# child3.net
KiCad netlist of a schematic drawn in Altium Designer
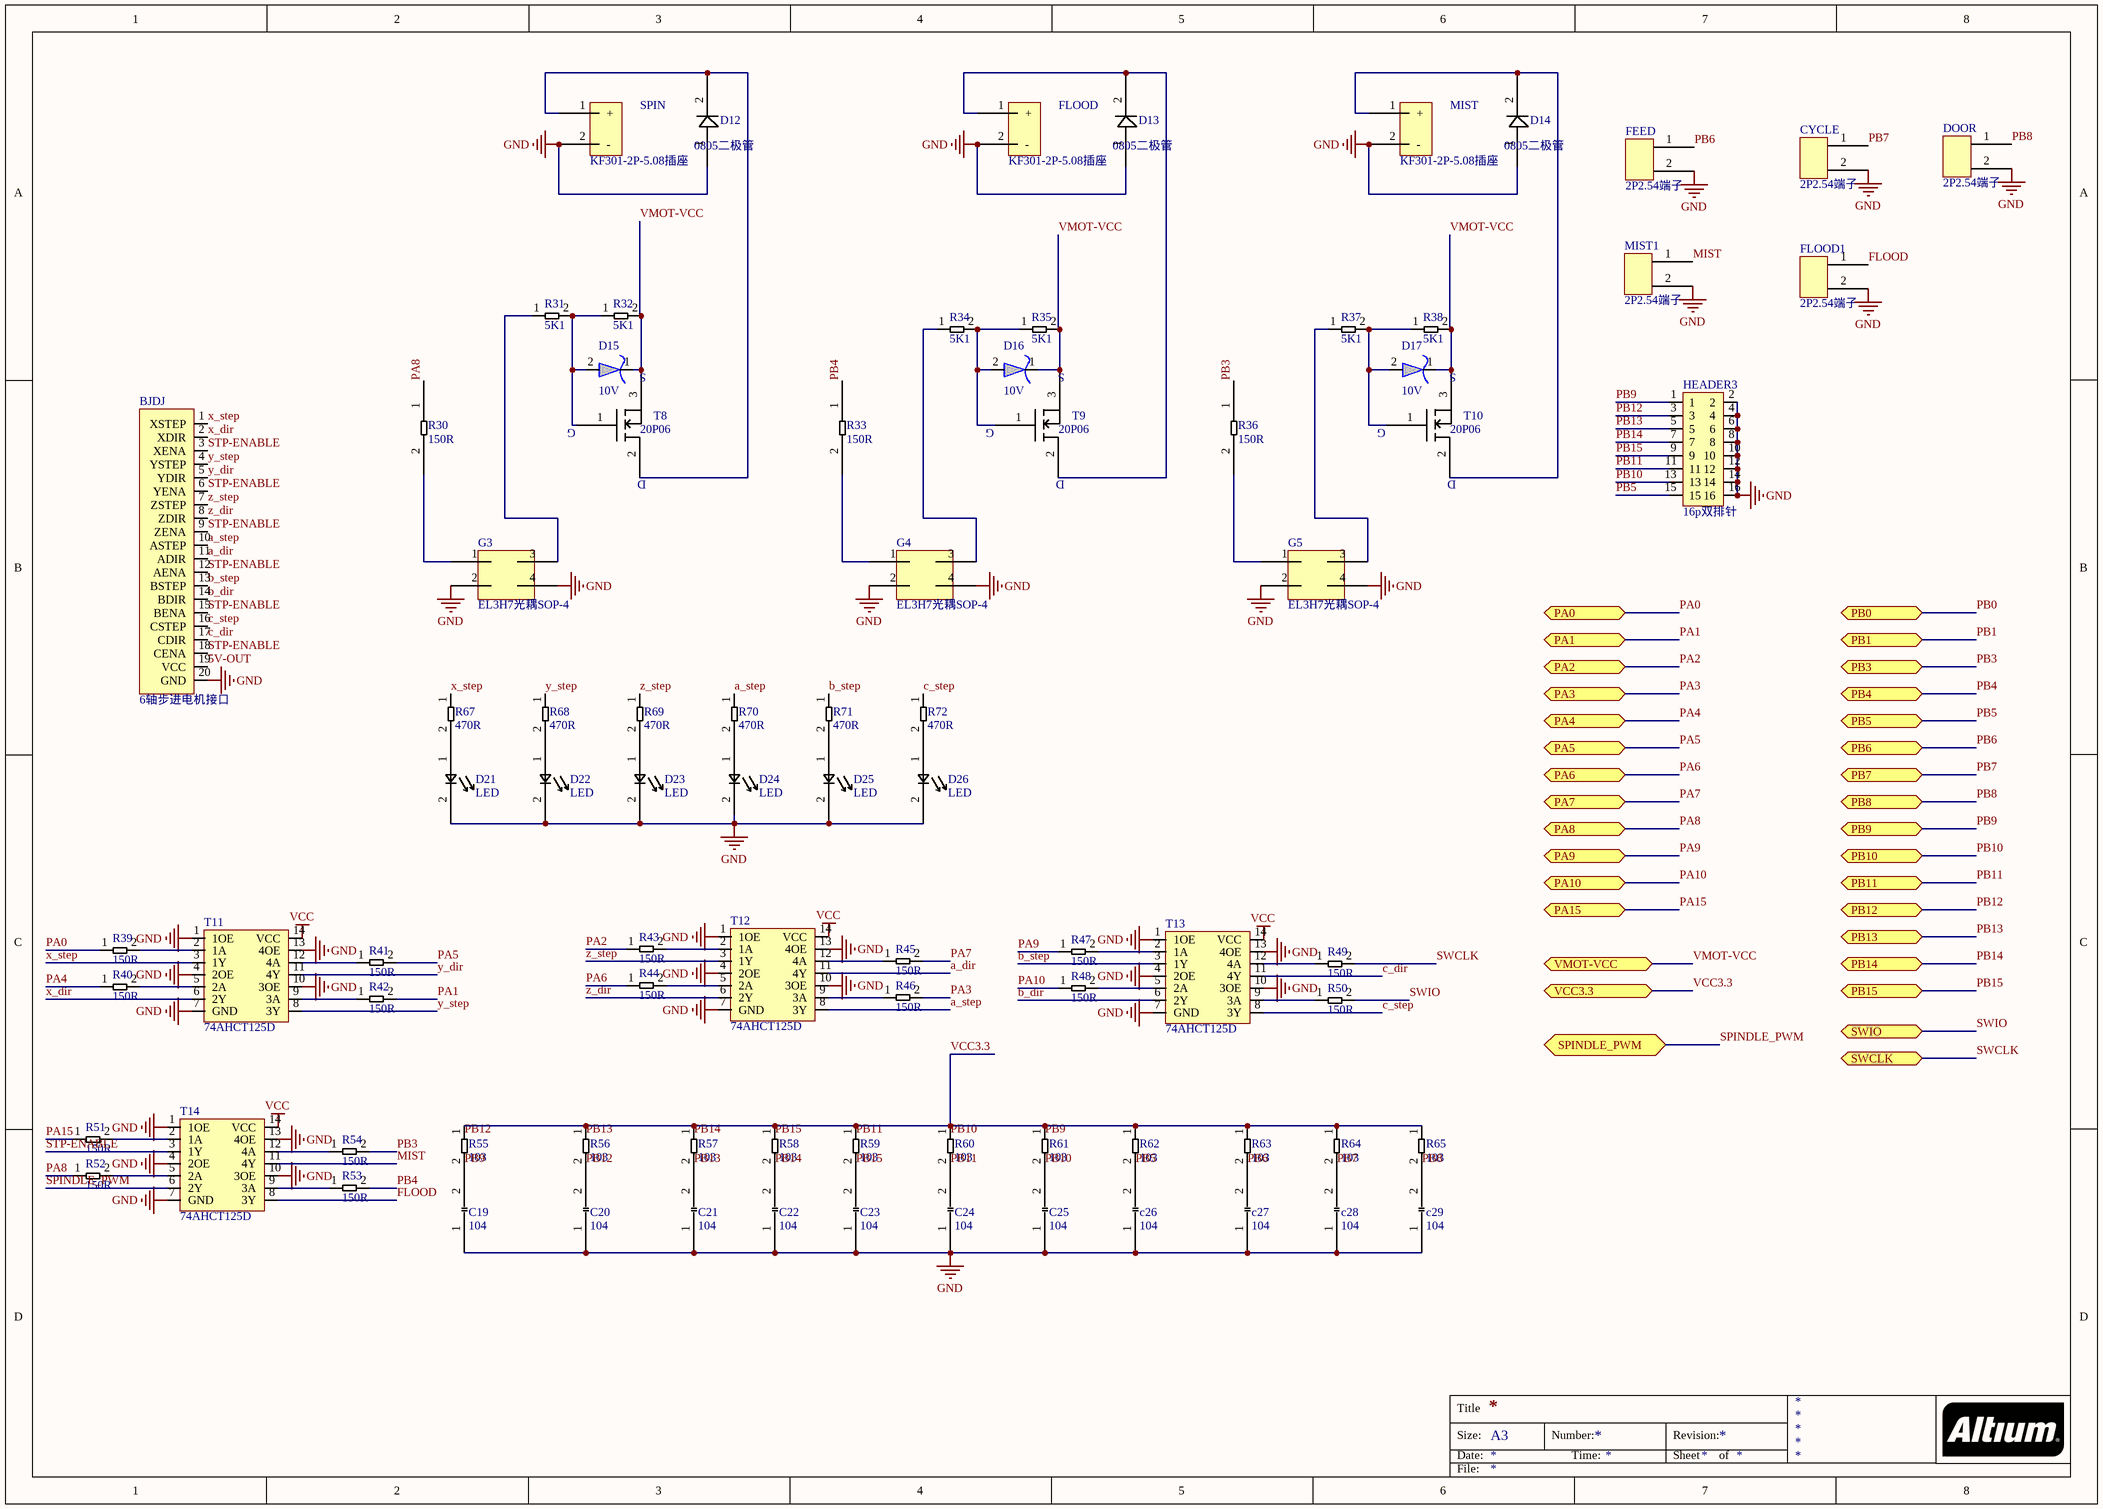
[diagram p0: child3.SchDoc]

(export (version "E")
  (design (tool "Eeschema 10.0.6"))
  (components
    (comp (ref "BJDJ") (value "6轴步进电机接口") (footprint "KF301-20P") (libsource (lib "51单片机") (part "6轴步进电机接口")))
    (comp (ref "C19") (value "104") (footprint "0805电容") (libsource (lib "51单片机") (part "0805贴片电容")))
    (comp (ref "C20") (value "104") (footprint "0805电容") (libsource (lib "51单片机") (part "0805贴片电容")))
    (comp (ref "C21") (value "104") (footprint "0805电容") (libsource (lib "51单片机") (part "0805贴片电容")))
    (comp (ref "C22") (value "104") (footprint "0805电容") (libsource (lib "51单片机") (part "0805贴片电容")))
    (comp (ref "C23") (value "104") (footprint "0805电容") (libsource (lib "51单片机") (part "0805贴片电容")))
    (comp (ref "C24") (value "104") (footprint "0805电容") (libsource (lib "51单片机") (part "0805贴片电容")))
    (comp (ref "C25") (value "104") (footprint "0805电容") (libsource (lib "51单片机") (part "0805贴片电容")))
    (comp (ref "c26") (value "104") (footprint "0805电容") (libsource (lib "51单片机") (part "0805贴片电容")))
    (comp (ref "c27") (value "104") (footprint "0805电容") (libsource (lib "51单片机") (part "0805贴片电容")))
    (comp (ref "c28") (value "104") (footprint "0805电容") (libsource (lib "51单片机") (part "0805贴片电容")))
    (comp (ref "c29") (value "104") (footprint "0805电容") (libsource (lib "51单片机") (part "0805贴片电容")))
    (comp (ref "CYCLE") (value "2P2.54端子") (footprint "2p2.54端子") (libsource (lib "51单片机") (part "2P2.54端子")))
    (comp (ref "D12") (value "0805二极管") (footprint "0805-二极管") (libsource (lib "51单片机") (part "0805二极管")))
    (comp (ref "D13") (value "0805二极管") (footprint "0805-二极管") (libsource (lib "51单片机") (part "0805二极管")))
    (comp (ref "D14") (value "0805二极管") (footprint "0805-二极管") (libsource (lib "51单片机") (part "0805二极管")))
    (comp (ref "D15") (value "10V") (footprint "1/2w贴片稳压二极管") (libsource (lib "51单片机") (part "贴片稳压二极管")))
    (comp (ref "D16") (value "10V") (footprint "1/2w贴片稳压二极管") (libsource (lib "51单片机") (part "贴片稳压二极管")))
    (comp (ref "D17") (value "10V") (footprint "1/2w贴片稳压二极管") (libsource (lib "51单片机") (part "贴片稳压二极管")))
    (comp (ref "D21") (value "LED") (footprint "0805二极管") (libsource (lib "51单片机") (part "0805贴片发光二极管")))
    (comp (ref "D22") (value "LED") (footprint "0805二极管") (libsource (lib "51单片机") (part "0805贴片发光二极管")))
    (comp (ref "D23") (value "LED") (footprint "0805二极管") (libsource (lib "51单片机") (part "0805贴片发光二极管")))
    (comp (ref "D24") (value "LED") (footprint "0805二极管") (libsource (lib "51单片机") (part "0805贴片发光二极管")))
    (comp (ref "D25") (value "LED") (footprint "0805二极管") (libsource (lib "51单片机") (part "0805贴片发光二极管")))
    (comp (ref "D26") (value "LED") (footprint "0805二极管") (libsource (lib "51单片机") (part "0805贴片发光二极管")))
    (comp (ref "DOOR") (value "2P2.54端子") (footprint "2p2.54端子") (libsource (lib "51单片机") (part "2P2.54端子")))
    (comp (ref "FEED") (value "2P2.54端子") (footprint "2p2.54端子") (libsource (lib "51单片机") (part "2P2.54端子")))
    (comp (ref "FLOOD")
      (value "KF301-2P-5.08插座")
      (footprint "KF301-2P-5.08插座")
      (libsource (lib "51单片机") (part "KF301-2P-5.08插座"))
    )
    (comp (ref "FLOOD1")
      (value "2P2.54端子")
      (footprint "2p2.54端子")
      (libsource (lib "51单片机") (part "2P2.54端子"))
    )
    (comp (ref "G3")
      (value "EL3H7光耦SOP-4")
      (footprint "EL3H7SOP-4")
      (libsource (lib "51单片机") (part "EL3H7光耦SOP-4"))
    )
    (comp (ref "G4")
      (value "EL3H7光耦SOP-4")
      (footprint "EL3H7SOP-4")
      (libsource (lib "51单片机") (part "EL3H7光耦SOP-4"))
    )
    (comp (ref "G5")
      (value "EL3H7光耦SOP-4")
      (footprint "EL3H7SOP-4")
      (libsource (lib "51单片机") (part "EL3H7光耦SOP-4"))
    )
    (comp (ref "HEADER3") (value "16p双排针") (footprint "16p双排针") (libsource (lib "51单片机") (part "16p双排针")))
    (comp (ref "MIST")
      (value "KF301-2P-5.08插座")
      (footprint "KF301-2P-5.08插座")
      (libsource (lib "51单片机") (part "KF301-2P-5.08插座"))
    )
    (comp (ref "MIST1") (value "2P2.54端子") (footprint "2p2.54端子") (libsource (lib "51单片机") (part "2P2.54端子")))
    (comp (ref "R30") (value "150R") (footprint "0805电阻") (libsource (lib "") (part "0805贴片电阻_1")))
    (comp (ref "R31") (value "5K1") (footprint "0805电阻") (libsource (lib "51单片机") (part "0805贴片电阻")))
    (comp (ref "R32") (value "5K1") (footprint "0805电阻") (libsource (lib "51单片机") (part "0805贴片电阻")))
    (comp (ref "R33") (value "150R") (footprint "0805电阻") (libsource (lib "") (part "0805贴片电阻_1")))
    (comp (ref "R34") (value "5K1") (footprint "0805电阻") (libsource (lib "51单片机") (part "0805贴片电阻")))
    (comp (ref "R35") (value "5K1") (footprint "0805电阻") (libsource (lib "51单片机") (part "0805贴片电阻")))
    (comp (ref "R36") (value "150R") (footprint "0805电阻") (libsource (lib "") (part "0805贴片电阻_1")))
    (comp (ref "R37") (value "5K1") (footprint "0805电阻") (libsource (lib "51单片机") (part "0805贴片电阻")))
    (comp (ref "R38") (value "5K1") (footprint "0805电阻") (libsource (lib "51单片机") (part "0805贴片电阻")))
    (comp (ref "R39") (value "150R") (footprint "0805电阻") (libsource (lib "51单片机") (part "0805贴片电阻")))
    (comp (ref "R40") (value "150R") (footprint "0805电阻") (libsource (lib "51单片机") (part "0805贴片电阻")))
    (comp (ref "R41") (value "150R") (footprint "0805电阻") (libsource (lib "51单片机") (part "0805贴片电阻")))
    (comp (ref "R42") (value "150R") (footprint "0805电阻") (libsource (lib "51单片机") (part "0805贴片电阻")))
    (comp (ref "R43") (value "150R") (footprint "0805电阻") (libsource (lib "51单片机") (part "0805贴片电阻")))
    (comp (ref "R44") (value "150R") (footprint "0805电阻") (libsource (lib "51单片机") (part "0805贴片电阻")))
    (comp (ref "R45") (value "150R") (footprint "0805电阻") (libsource (lib "51单片机") (part "0805贴片电阻")))
    (comp (ref "R46") (value "150R") (footprint "0805电阻") (libsource (lib "51单片机") (part "0805贴片电阻")))
    (comp (ref "R47") (value "150R") (footprint "0805电阻") (libsource (lib "51单片机") (part "0805贴片电阻")))
    (comp (ref "R48") (value "150R") (footprint "0805电阻") (libsource (lib "51单片机") (part "0805贴片电阻")))
    (comp (ref "R49") (value "150R") (footprint "0805电阻") (libsource (lib "51单片机") (part "0805贴片电阻")))
    (comp (ref "R50") (value "150R") (footprint "0805电阻") (libsource (lib "51单片机") (part "0805贴片电阻")))
    (comp (ref "R51") (value "150R") (footprint "0805电阻") (libsource (lib "51单片机") (part "0805贴片电阻")))
    (comp (ref "R52") (value "150R") (footprint "0805电阻") (libsource (lib "51单片机") (part "0805贴片电阻")))
    (comp (ref "R53") (value "150R") (footprint "0805电阻") (libsource (lib "51单片机") (part "0805贴片电阻")))
    (comp (ref "R54") (value "150R") (footprint "0805电阻") (libsource (lib "51单片机") (part "0805贴片电阻")))
    (comp (ref "R55") (value "103") (footprint "0805电阻") (libsource (lib "51单片机") (part "0805贴片电阻")))
    (comp (ref "R56") (value "103") (footprint "0805电阻") (libsource (lib "51单片机") (part "0805贴片电阻")))
    (comp (ref "R57") (value "103") (footprint "0805电阻") (libsource (lib "51单片机") (part "0805贴片电阻")))
    (comp (ref "R58") (value "103") (footprint "0805电阻") (libsource (lib "51单片机") (part "0805贴片电阻")))
    (comp (ref "R59") (value "103") (footprint "0805电阻") (libsource (lib "51单片机") (part "0805贴片电阻")))
    (comp (ref "R60") (value "103") (footprint "0805电阻") (libsource (lib "51单片机") (part "0805贴片电阻")))
    (comp (ref "R61") (value "103") (footprint "0805电阻") (libsource (lib "51单片机") (part "0805贴片电阻")))
    (comp (ref "R62") (value "103") (footprint "0805电阻") (libsource (lib "51单片机") (part "0805贴片电阻")))
    (comp (ref "R63") (value "103") (footprint "0805电阻") (libsource (lib "51单片机") (part "0805贴片电阻")))
    (comp (ref "R64") (value "103") (footprint "0805电阻") (libsource (lib "51单片机") (part "0805贴片电阻")))
    (comp (ref "R65") (value "103") (footprint "0805电阻") (libsource (lib "51单片机") (part "0805贴片电阻")))
    (comp (ref "R67") (value "470R") (footprint "0805电阻") (libsource (lib "51单片机") (part "0805贴片电阻")))
    (comp (ref "R68") (value "470R") (footprint "0805电阻") (libsource (lib "51单片机") (part "0805贴片电阻")))
    (comp (ref "R69") (value "470R") (footprint "0805电阻") (libsource (lib "51单片机") (part "0805贴片电阻")))
    (comp (ref "R70") (value "470R") (footprint "0805电阻") (libsource (lib "51单片机") (part "0805贴片电阻")))
    (comp (ref "R71") (value "470R") (footprint "0805电阻") (libsource (lib "51单片机") (part "0805贴片电阻")))
    (comp (ref "R72") (value "470R") (footprint "0805电阻") (libsource (lib "51单片机") (part "0805贴片电阻")))
    (comp (ref "SPIN")
      (value "KF301-2P-5.08插座")
      (footprint "KF301-2P-5.08插座")
      (libsource (lib "51单片机") (part "KF301-2P-5.08插座"))
    )
    (comp (ref "T8") (value "20P06") (footprint "to-252") (libsource (lib "51单片机") (part "20P06场效应管")))
    (comp (ref "T9") (value "20P06") (footprint "to-252") (libsource (lib "51单片机") (part "20P06场效应管")))
    (comp (ref "T10") (value "20P06") (footprint "to-252") (libsource (lib "51单片机") (part "20P06场效应管")))
    (comp (ref "T11") (value "74AHCT125D") (footprint "SOIC14") (libsource (lib "51单片机") (part "74AHC125D")))
    (comp (ref "T12") (value "74AHCT125D") (footprint "SOIC14") (libsource (lib "51单片机") (part "74AHC125D")))
    (comp (ref "T13") (value "74AHCT125D") (footprint "SOIC14") (libsource (lib "51单片机") (part "74AHC125D")))
    (comp (ref "T14") (value "74AHCT125D") (footprint "SOIC14") (libsource (lib "51单片机") (part "74AHC125D")))
  )
  (nets
    (net (code "1") (name "/5V-OUT") (class "Default")
      (node (ref "BJDJ") (pin "19") (pinfunction "VCC_19") (pintype "passive"))
    )
    (net (code "2") (name "/FLOOD") (class "Default")
      (node (ref "FLOOD1") (pin "1") (pintype "passive"))
      (node (ref "T14") (pin "8") (pinfunction "3Y_8") (pintype "passive"))
    )
    (net (code "3") (name "/MIST") (class "Default")
      (node (ref "MIST1") (pin "1") (pintype "passive"))
      (node (ref "T14") (pin "11") (pinfunction "4Y_11") (pintype "passive"))
    )
    (net (code "4") (name "/PA0") (class "Default") (node (ref "R39") (pin "1") (pintype "passive")))
    (net (code "5") (name "/PA1") (class "Default") (node (ref "R42") (pin "2") (pintype "passive")))
    (net (code "6") (name "/PA2") (class "Default") (node (ref "R43") (pin "1") (pintype "passive")))
    (net (code "7") (name "/PA3") (class "Default") (node (ref "R46") (pin "2") (pintype "passive")))
    (net (code "8") (name "/PA4") (class "Default") (node (ref "R40") (pin "1") (pintype "passive")))
    (net (code "9") (name "/PA5") (class "Default") (node (ref "R41") (pin "2") (pintype "passive")))
    (net (code "10") (name "/PA6") (class "Default") (node (ref "R44") (pin "1") (pintype "passive")))
    (net (code "11") (name "/PA7") (class "Default") (node (ref "R45") (pin "2") (pintype "passive")))
    (net (code "12") (name "/PA8") (class "Default")
      (node (ref "R30") (pin "1") (pintype "passive"))
      (node (ref "R52") (pin "1") (pintype "passive"))
    )
    (net (code "13") (name "/PA9") (class "Default") (node (ref "R47") (pin "1") (pintype "passive")))
    (net (code "14") (name "/PA10") (class "Default") (node (ref "R48") (pin "1") (pintype "passive")))
    (net (code "15") (name "/PA15") (class "Default") (node (ref "R51") (pin "1") (pintype "passive")))
    (net (code "18") (name "/PB3") (class "Default")
      (node (ref "R36") (pin "1") (pintype "passive"))
      (node (ref "R54") (pin "2") (pintype "passive"))
    )
    (net (code "19") (name "/PB4") (class "Default")
      (node (ref "R33") (pin "1") (pintype "passive"))
      (node (ref "R53") (pin "2") (pintype "passive"))
    )
    (net (code "20") (name "/PB5") (class "Default")
      (node (ref "HEADER3") (pin "15") (pinfunction "15_15") (pintype "passive"))
      (node (ref "R62") (pin "2") (pintype "passive"))
      (node (ref "c26") (pin "2") (pintype "passive"))
    )
    (net (code "21") (name "/PB6") (class "Default")
      (node (ref "FEED") (pin "1") (pintype "passive"))
      (node (ref "R63") (pin "2") (pintype "passive"))
      (node (ref "c27") (pin "2") (pintype "passive"))
    )
    (net (code "22") (name "/PB7") (class "Default")
      (node (ref "CYCLE") (pin "1") (pintype "passive"))
      (node (ref "R64") (pin "2") (pintype "passive"))
      (node (ref "c28") (pin "2") (pintype "passive"))
    )
    (net (code "23") (name "/PB8") (class "Default")
      (node (ref "DOOR") (pin "1") (pintype "passive"))
      (node (ref "R65") (pin "2") (pintype "passive"))
      (node (ref "c29") (pin "2") (pintype "passive"))
    )
    (net (code "24") (name "/PB9") (class "Default")
      (node (ref "C19") (pin "2") (pintype "passive"))
      (node (ref "HEADER3") (pin "1") (pinfunction "1_1") (pintype "passive"))
      (node (ref "R55") (pin "2") (pintype "passive"))
    )
    (net (code "25") (name "/PB10") (class "Default")
      (node (ref "C25") (pin "2") (pintype "passive"))
      (node (ref "HEADER3") (pin "13") (pinfunction "13_13") (pintype "passive"))
      (node (ref "R61") (pin "2") (pintype "passive"))
    )
    (net (code "26") (name "/PB11") (class "Default")
      (node (ref "C24") (pin "2") (pintype "passive"))
      (node (ref "HEADER3") (pin "11") (pinfunction "11_11") (pintype "passive"))
      (node (ref "R60") (pin "2") (pintype "passive"))
    )
    (net (code "27") (name "/PB12") (class "Default")
      (node (ref "C20") (pin "2") (pintype "passive"))
      (node (ref "HEADER3") (pin "3") (pinfunction "3_3") (pintype "passive"))
      (node (ref "R56") (pin "2") (pintype "passive"))
    )
    (net (code "28") (name "/PB13") (class "Default")
      (node (ref "C21") (pin "2") (pintype "passive"))
      (node (ref "HEADER3") (pin "5") (pinfunction "5_5") (pintype "passive"))
      (node (ref "R57") (pin "2") (pintype "passive"))
    )
    (net (code "29") (name "/PB14") (class "Default")
      (node (ref "C22") (pin "2") (pintype "passive"))
      (node (ref "HEADER3") (pin "7") (pinfunction "7_7") (pintype "passive"))
      (node (ref "R58") (pin "2") (pintype "passive"))
    )
    (net (code "30") (name "/PB15") (class "Default")
      (node (ref "C23") (pin "2") (pintype "passive"))
      (node (ref "HEADER3") (pin "9") (pinfunction "9_9") (pintype "passive"))
      (node (ref "R59") (pin "2") (pintype "passive"))
    )
    (net (code "31") (name "/SPINDLE_PWM") (class "Default")
      (node (ref "T14") (pin "6") (pinfunction "2Y_6") (pintype "passive"))
    )
    (net (code "32") (name "/STP-ENABLE") (class "Default")
      (node (ref "BJDJ") (pin "12") (pinfunction "AENA_12") (pintype "passive"))
      (node (ref "BJDJ") (pin "15") (pinfunction "BENA_15") (pintype "passive"))
      (node (ref "BJDJ") (pin "18") (pinfunction "CENA_18") (pintype "passive"))
      (node (ref "BJDJ") (pin "3") (pinfunction "XENA_3") (pintype "passive"))
      (node (ref "BJDJ") (pin "6") (pinfunction "YENA_6") (pintype "passive"))
      (node (ref "BJDJ") (pin "9") (pinfunction "ZENA_9") (pintype "passive"))
      (node (ref "T14") (pin "3") (pinfunction "1Y_3") (pintype "passive"))
    )
    (net (code "33") (name "/SWCLK") (class "Default") (node (ref "R49") (pin "2") (pintype "passive")))
    (net (code "34") (name "/SWIO") (class "Default") (node (ref "R50") (pin "2") (pintype "passive")))
    (net (code "35") (name "/VCC3.3") (class "Default")
      (node (ref "R55") (pin "1") (pintype "passive"))
      (node (ref "R56") (pin "1") (pintype "passive"))
      (node (ref "R57") (pin "1") (pintype "passive"))
      (node (ref "R58") (pin "1") (pintype "passive"))
      (node (ref "R59") (pin "1") (pintype "passive"))
      (node (ref "R60") (pin "1") (pintype "passive"))
      (node (ref "R61") (pin "1") (pintype "passive"))
      (node (ref "R62") (pin "1") (pintype "passive"))
      (node (ref "R63") (pin "1") (pintype "passive"))
      (node (ref "R64") (pin "1") (pintype "passive"))
      (node (ref "R65") (pin "1") (pintype "passive"))
    )
    (net (code "36") (name "/VMOT-VCC") (class "Default")
      (node (ref "D15") (pin "1") (pintype "passive"))
      (node (ref "D16") (pin "1") (pintype "passive"))
      (node (ref "D17") (pin "1") (pintype "passive"))
      (node (ref "R32") (pin "2") (pintype "passive"))
      (node (ref "R35") (pin "2") (pintype "passive"))
      (node (ref "R38") (pin "2") (pintype "passive"))
      (node (ref "T10") (pin "3") (pintype "passive"))
      (node (ref "T8") (pin "3") (pintype "passive"))
      (node (ref "T9") (pin "3") (pintype "passive"))
    )
    (net (code "37") (name "/a_dir") (class "Default")
      (node (ref "BJDJ") (pin "11") (pinfunction "ADIR_11") (pintype "passive"))
      (node (ref "T12") (pin "11") (pinfunction "4Y_11") (pintype "passive"))
    )
    (net (code "38") (name "/a_step") (class "Default")
      (node (ref "BJDJ") (pin "10") (pinfunction "ASTEP_10") (pintype "passive"))
      (node (ref "R70") (pin "1") (pintype "passive"))
      (node (ref "T12") (pin "8") (pinfunction "3Y_8") (pintype "passive"))
    )
    (net (code "39") (name "/b_dir") (class "Default")
      (node (ref "BJDJ") (pin "14") (pinfunction "BDIR_14") (pintype "passive"))
      (node (ref "T13") (pin "6") (pinfunction "2Y_6") (pintype "passive"))
    )
    (net (code "40") (name "/b_step") (class "Default")
      (node (ref "BJDJ") (pin "13") (pinfunction "BSTEP_13") (pintype "passive"))
      (node (ref "R71") (pin "1") (pintype "passive"))
      (node (ref "T13") (pin "3") (pinfunction "1Y_3") (pintype "passive"))
    )
    (net (code "41") (name "/c_dir") (class "Default")
      (node (ref "BJDJ") (pin "17") (pinfunction "CDIR_17") (pintype "passive"))
      (node (ref "T13") (pin "11") (pinfunction "4Y_11") (pintype "passive"))
    )
    (net (code "42") (name "/c_step") (class "Default")
      (node (ref "BJDJ") (pin "16") (pinfunction "CSTEP_16") (pintype "passive"))
      (node (ref "R72") (pin "1") (pintype "passive"))
      (node (ref "T13") (pin "8") (pinfunction "3Y_8") (pintype "passive"))
    )
    (net (code "43") (name "/x_dir") (class "Default")
      (node (ref "BJDJ") (pin "2") (pinfunction "XDIR_2") (pintype "passive"))
      (node (ref "T11") (pin "6") (pinfunction "2Y_6") (pintype "passive"))
    )
    (net (code "44") (name "/x_step") (class "Default")
      (node (ref "BJDJ") (pin "1") (pinfunction "XSTEP_1") (pintype "passive"))
      (node (ref "R67") (pin "1") (pintype "passive"))
      (node (ref "T11") (pin "3") (pinfunction "1Y_3") (pintype "passive"))
    )
    (net (code "45") (name "/y_dir") (class "Default")
      (node (ref "BJDJ") (pin "5") (pinfunction "YDIR_5") (pintype "passive"))
      (node (ref "T11") (pin "11") (pinfunction "4Y_11") (pintype "passive"))
    )
    (net (code "46") (name "/y_step") (class "Default")
      (node (ref "BJDJ") (pin "4") (pinfunction "YSTEP_4") (pintype "passive"))
      (node (ref "R68") (pin "1") (pintype "passive"))
      (node (ref "T11") (pin "8") (pinfunction "3Y_8") (pintype "passive"))
    )
    (net (code "47") (name "/z_dir") (class "Default")
      (node (ref "BJDJ") (pin "8") (pinfunction "ZDIR_8") (pintype "passive"))
      (node (ref "T12") (pin "6") (pinfunction "2Y_6") (pintype "passive"))
    )
    (net (code "48") (name "/z_step") (class "Default")
      (node (ref "BJDJ") (pin "7") (pinfunction "ZSTEP_7") (pintype "passive"))
      (node (ref "R69") (pin "1") (pintype "passive"))
      (node (ref "T12") (pin "3") (pinfunction "1Y_3") (pintype "passive"))
    )
    (net (code "49") (name "GND") (class "Default")
      (node (ref "BJDJ") (pin "20") (pinfunction "GND_20") (pintype "passive"))
      (node (ref "C19") (pin "1") (pintype "passive"))
      (node (ref "C20") (pin "1") (pintype "passive"))
      (node (ref "C21") (pin "1") (pintype "passive"))
      (node (ref "C22") (pin "1") (pintype "passive"))
      (node (ref "C23") (pin "1") (pintype "passive"))
      (node (ref "C24") (pin "1") (pintype "passive"))
      (node (ref "C25") (pin "1") (pintype "passive"))
      (node (ref "CYCLE") (pin "2") (pintype "passive"))
      (node (ref "D12") (pin "1") (pintype "passive"))
      (node (ref "D13") (pin "1") (pintype "passive"))
      (node (ref "D14") (pin "1") (pintype "passive"))
      (node (ref "D21") (pin "2") (pintype "passive"))
      (node (ref "D22") (pin "2") (pintype "passive"))
      (node (ref "D23") (pin "2") (pintype "passive"))
      (node (ref "D24") (pin "2") (pintype "passive"))
      (node (ref "D25") (pin "2") (pintype "passive"))
      (node (ref "D26") (pin "2") (pintype "passive"))
      (node (ref "DOOR") (pin "2") (pintype "passive"))
      (node (ref "FEED") (pin "2") (pintype "passive"))
      (node (ref "FLOOD") (pin "2") (pinfunction "-_2") (pintype "passive"))
      (node (ref "FLOOD1") (pin "2") (pintype "passive"))
      (node (ref "G3") (pin "2") (pintype "passive"))
      (node (ref "G3") (pin "4") (pintype "passive"))
      (node (ref "G4") (pin "2") (pintype "passive"))
      (node (ref "G4") (pin "4") (pintype "passive"))
      (node (ref "G5") (pin "2") (pintype "passive"))
      (node (ref "G5") (pin "4") (pintype "passive"))
      (node (ref "HEADER3") (pin "10") (pinfunction "10_10") (pintype "passive"))
      (node (ref "HEADER3") (pin "12") (pinfunction "12_12") (pintype "passive"))
      (node (ref "HEADER3") (pin "14") (pinfunction "14_14") (pintype "passive"))
      (node (ref "HEADER3") (pin "16") (pinfunction "16_16") (pintype "passive"))
      (node (ref "HEADER3") (pin "2") (pinfunction "2_2") (pintype "passive"))
      (node (ref "HEADER3") (pin "4") (pinfunction "4_4") (pintype "passive"))
      (node (ref "HEADER3") (pin "6") (pinfunction "6_6") (pintype "passive"))
      (node (ref "HEADER3") (pin "8") (pinfunction "8_8") (pintype "passive"))
      (node (ref "MIST") (pin "2") (pinfunction "-_2") (pintype "passive"))
      (node (ref "MIST1") (pin "2") (pintype "passive"))
      (node (ref "SPIN") (pin "2") (pinfunction "-_2") (pintype "passive"))
      (node (ref "T11") (pin "1") (pinfunction "1OE_1") (pintype "passive"))
      (node (ref "T11") (pin "10") (pinfunction "3OE_10") (pintype "passive"))
      (node (ref "T11") (pin "13") (pinfunction "4OE_13") (pintype "passive"))
      (node (ref "T11") (pin "4") (pinfunction "2OE_4") (pintype "passive"))
      (node (ref "T11") (pin "7") (pinfunction "GND_7") (pintype "passive"))
      (node (ref "T12") (pin "1") (pinfunction "1OE_1") (pintype "passive"))
      (node (ref "T12") (pin "10") (pinfunction "3OE_10") (pintype "passive"))
      (node (ref "T12") (pin "13") (pinfunction "4OE_13") (pintype "passive"))
      (node (ref "T12") (pin "4") (pinfunction "2OE_4") (pintype "passive"))
      (node (ref "T12") (pin "7") (pinfunction "GND_7") (pintype "passive"))
      (node (ref "T13") (pin "1") (pinfunction "1OE_1") (pintype "passive"))
      (node (ref "T13") (pin "10") (pinfunction "3OE_10") (pintype "passive"))
      (node (ref "T13") (pin "13") (pinfunction "4OE_13") (pintype "passive"))
      (node (ref "T13") (pin "4") (pinfunction "2OE_4") (pintype "passive"))
      (node (ref "T13") (pin "7") (pinfunction "GND_7") (pintype "passive"))
      (node (ref "T14") (pin "1") (pinfunction "1OE_1") (pintype "passive"))
      (node (ref "T14") (pin "10") (pinfunction "3OE_10") (pintype "passive"))
      (node (ref "T14") (pin "13") (pinfunction "4OE_13") (pintype "passive"))
      (node (ref "T14") (pin "4") (pinfunction "2OE_4") (pintype "passive"))
      (node (ref "T14") (pin "7") (pinfunction "GND_7") (pintype "passive"))
      (node (ref "c26") (pin "1") (pintype "passive"))
      (node (ref "c27") (pin "1") (pintype "passive"))
      (node (ref "c28") (pin "1") (pintype "passive"))
      (node (ref "c29") (pin "1") (pintype "passive"))
    )
    (net (code "50") (name "Net-(D15-Pad2)") (class "Default")
      (node (ref "D15") (pin "2") (pintype "passive"))
      (node (ref "R31") (pin "2") (pintype "passive"))
      (node (ref "R32") (pin "1") (pintype "passive"))
      (node (ref "T8") (pin "1") (pintype "passive"))
    )
    (net (code "51") (name "Net-(D16-Pad2)") (class "Default")
      (node (ref "D16") (pin "2") (pintype "passive"))
      (node (ref "R34") (pin "2") (pintype "passive"))
      (node (ref "R35") (pin "1") (pintype "passive"))
      (node (ref "T9") (pin "1") (pintype "passive"))
    )
    (net (code "52") (name "Net-(D17-Pad2)") (class "Default")
      (node (ref "D17") (pin "2") (pintype "passive"))
      (node (ref "R37") (pin "2") (pintype "passive"))
      (node (ref "R38") (pin "1") (pintype "passive"))
      (node (ref "T10") (pin "1") (pintype "passive"))
    )
    (net (code "53") (name "Net-(D21-Pad1)") (class "Default")
      (node (ref "D21") (pin "1") (pintype "passive"))
      (node (ref "R67") (pin "2") (pintype "passive"))
    )
    (net (code "54") (name "Net-(D22-Pad1)") (class "Default")
      (node (ref "D22") (pin "1") (pintype "passive"))
      (node (ref "R68") (pin "2") (pintype "passive"))
    )
    (net (code "55") (name "Net-(D23-Pad1)") (class "Default")
      (node (ref "D23") (pin "1") (pintype "passive"))
      (node (ref "R69") (pin "2") (pintype "passive"))
    )
    (net (code "56") (name "Net-(D24-Pad1)") (class "Default")
      (node (ref "D24") (pin "1") (pintype "passive"))
      (node (ref "R70") (pin "2") (pintype "passive"))
    )
    (net (code "57") (name "Net-(D25-Pad1)") (class "Default")
      (node (ref "D25") (pin "1") (pintype "passive"))
      (node (ref "R71") (pin "2") (pintype "passive"))
    )
    (net (code "58") (name "Net-(D26-Pad1)") (class "Default")
      (node (ref "D26") (pin "1") (pintype "passive"))
      (node (ref "R72") (pin "2") (pintype "passive"))
    )
    (net (code "59") (name "Net-(FLOOD-+)") (class "Default")
      (node (ref "D13") (pin "2") (pintype "passive"))
      (node (ref "FLOOD") (pin "1") (pinfunction "+_1") (pintype "passive"))
      (node (ref "T9") (pin "2") (pintype "passive"))
    )
    (net (code "60") (name "Net-(G3-Pad1)") (class "Default")
      (node (ref "G3") (pin "1") (pintype "passive"))
      (node (ref "R30") (pin "2") (pintype "passive"))
    )
    (net (code "61") (name "Net-(G3-Pad3)") (class "Default")
      (node (ref "G3") (pin "3") (pintype "passive"))
      (node (ref "R31") (pin "1") (pintype "passive"))
    )
    (net (code "62") (name "Net-(G4-Pad1)") (class "Default")
      (node (ref "G4") (pin "1") (pintype "passive"))
      (node (ref "R33") (pin "2") (pintype "passive"))
    )
    (net (code "63") (name "Net-(G4-Pad3)") (class "Default")
      (node (ref "G4") (pin "3") (pintype "passive"))
      (node (ref "R34") (pin "1") (pintype "passive"))
    )
    (net (code "64") (name "Net-(G5-Pad1)") (class "Default")
      (node (ref "G5") (pin "1") (pintype "passive"))
      (node (ref "R36") (pin "2") (pintype "passive"))
    )
    (net (code "65") (name "Net-(G5-Pad3)") (class "Default")
      (node (ref "G5") (pin "3") (pintype "passive"))
      (node (ref "R37") (pin "1") (pintype "passive"))
    )
    (net (code "66") (name "Net-(MIST-+)") (class "Default")
      (node (ref "D14") (pin "2") (pintype "passive"))
      (node (ref "MIST") (pin "1") (pinfunction "+_1") (pintype "passive"))
      (node (ref "T10") (pin "2") (pintype "passive"))
    )
    (net (code "67") (name "Net-(SPIN-+)") (class "Default")
      (node (ref "D12") (pin "2") (pintype "passive"))
      (node (ref "SPIN") (pin "1") (pinfunction "+_1") (pintype "passive"))
      (node (ref "T8") (pin "2") (pintype "passive"))
    )
    (net (code "68") (name "Net-(T11-1A)") (class "Default")
      (node (ref "R39") (pin "2") (pintype "passive"))
      (node (ref "T11") (pin "2") (pinfunction "1A_2") (pintype "passive"))
    )
    (net (code "69") (name "Net-(T11-2A)") (class "Default")
      (node (ref "R40") (pin "2") (pintype "passive"))
      (node (ref "T11") (pin "5") (pinfunction "2A_5") (pintype "passive"))
    )
    (net (code "70") (name "Net-(T11-3A)") (class "Default")
      (node (ref "R42") (pin "1") (pintype "passive"))
      (node (ref "T11") (pin "9") (pinfunction "3A_9") (pintype "passive"))
    )
    (net (code "71") (name "Net-(T11-4A)") (class "Default")
      (node (ref "R41") (pin "1") (pintype "passive"))
      (node (ref "T11") (pin "12") (pinfunction "4A_12") (pintype "passive"))
    )
    (net (code "72") (name "Net-(T12-1A)") (class "Default")
      (node (ref "R43") (pin "2") (pintype "passive"))
      (node (ref "T12") (pin "2") (pinfunction "1A_2") (pintype "passive"))
    )
    (net (code "73") (name "Net-(T12-2A)") (class "Default")
      (node (ref "R44") (pin "2") (pintype "passive"))
      (node (ref "T12") (pin "5") (pinfunction "2A_5") (pintype "passive"))
    )
    (net (code "74") (name "Net-(T12-3A)") (class "Default")
      (node (ref "R46") (pin "1") (pintype "passive"))
      (node (ref "T12") (pin "9") (pinfunction "3A_9") (pintype "passive"))
    )
    (net (code "75") (name "Net-(T12-4A)") (class "Default")
      (node (ref "R45") (pin "1") (pintype "passive"))
      (node (ref "T12") (pin "12") (pinfunction "4A_12") (pintype "passive"))
    )
    (net (code "76") (name "Net-(T13-1A)") (class "Default")
      (node (ref "R47") (pin "2") (pintype "passive"))
      (node (ref "T13") (pin "2") (pinfunction "1A_2") (pintype "passive"))
    )
    (net (code "77") (name "Net-(T13-2A)") (class "Default")
      (node (ref "R48") (pin "2") (pintype "passive"))
      (node (ref "T13") (pin "5") (pinfunction "2A_5") (pintype "passive"))
    )
    (net (code "78") (name "Net-(T13-3A)") (class "Default")
      (node (ref "R50") (pin "1") (pintype "passive"))
      (node (ref "T13") (pin "9") (pinfunction "3A_9") (pintype "passive"))
    )
    (net (code "79") (name "Net-(T13-4A)") (class "Default")
      (node (ref "R49") (pin "1") (pintype "passive"))
      (node (ref "T13") (pin "12") (pinfunction "4A_12") (pintype "passive"))
    )
    (net (code "80") (name "Net-(T14-1A)") (class "Default")
      (node (ref "R51") (pin "2") (pintype "passive"))
      (node (ref "T14") (pin "2") (pinfunction "1A_2") (pintype "passive"))
    )
    (net (code "81") (name "Net-(T14-2A)") (class "Default")
      (node (ref "R52") (pin "2") (pintype "passive"))
      (node (ref "T14") (pin "5") (pinfunction "2A_5") (pintype "passive"))
    )
    (net (code "82") (name "Net-(T14-3A)") (class "Default")
      (node (ref "R53") (pin "1") (pintype "passive"))
      (node (ref "T14") (pin "9") (pinfunction "3A_9") (pintype "passive"))
    )
    (net (code "83") (name "Net-(T14-4A)") (class "Default")
      (node (ref "R54") (pin "1") (pintype "passive"))
      (node (ref "T14") (pin "12") (pinfunction "4A_12") (pintype "passive"))
    )
    (net (code "84") (name "VCC") (class "Default")
      (node (ref "T11") (pin "14") (pinfunction "VCC_14") (pintype "passive"))
      (node (ref "T12") (pin "14") (pinfunction "VCC_14") (pintype "passive"))
      (node (ref "T13") (pin "14") (pinfunction "VCC_14") (pintype "passive"))
      (node (ref "T14") (pin "14") (pinfunction "VCC_14") (pintype "passive"))
    )
  )
)
